# Main.net
KiCad netlist of a schematic drawn in Altium Designer
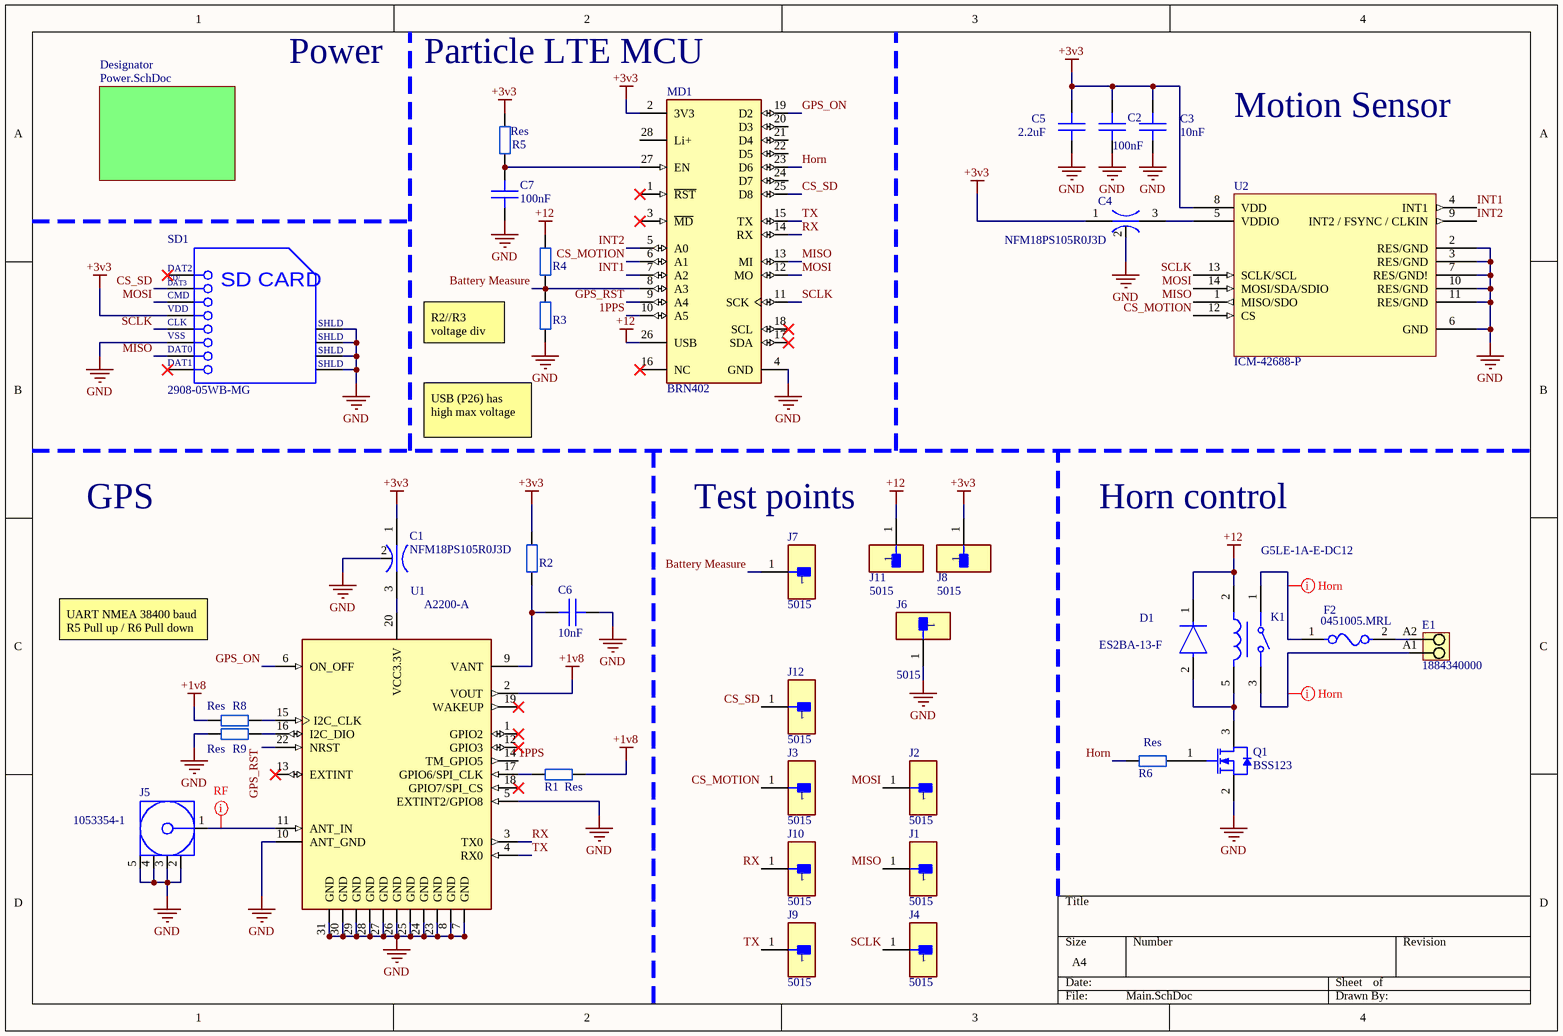
[diagram p0: Main.SchDoc]

(export (version "E")
  (design (tool "Eeschema 10.0.6"))
  (components
    (comp (ref "C1")
      (value "NFM18PS105R0J3D")
      (footprint "FP-NFM18-0_1-e0_05_0_35-MFG")
      (fields (field (name "VOLTAGE") "6.3V") (field (name "TOLERANCE") "20%"))
      (libsource (lib "Altium Content Vault") (part "2c8219d808f9f7a44d846a7a664b4f6"))
    )
    (comp (ref "C2")
      (value "100nF")
      (footprint "C0603 (1608)")
      (fields (field (name "Comment") "Cap SMD"))
      (libsource (lib "Moto Symbol Lib") (part "Cap SMD"))
    )
    (comp (ref "C3")
      (value "10nF")
      (footprint "C0603 (1608)")
      (fields (field (name "Comment") "Cap SMD"))
      (libsource (lib "Moto Symbol Lib") (part "Cap SMD"))
    )
    (comp (ref "C4")
      (value "NFM18PS105R0J3D")
      (footprint "FP-NFM18-0_1-e0_05_0_35-MFG")
      (fields (field (name "VOLTAGE") "6.3V") (field (name "TOLERANCE") "20%"))
      (libsource (lib "Altium Content Vault") (part "2c8219d808f9f7a44d846a7a664b4f6"))
    )
    (comp (ref "C5")
      (value "2.2uF")
      (footprint "C0603 (1608)")
      (fields (field (name "Comment") "Cap SMD"))
      (libsource (lib "Moto Symbol Lib") (part "Cap SMD"))
    )
    (comp (ref "C6")
      (value "10nF")
      (footprint "C0603 (1608)")
      (fields (field (name "Comment") "Cap SMD"))
      (libsource (lib "Moto Symbol Lib") (part "Cap SMD"))
    )
    (comp (ref "C7")
      (value "100nF")
      (footprint "C0603 (1608)")
      (fields (field (name "Comment") "Cap SMD"))
      (libsource (lib "Moto Symbol Lib") (part "Cap SMD"))
    )
    (comp (ref "D1")
      (value "ES2BA-13-F")
      (footprint "FP-SMA-MFG")
      (description "DIODE GEN PURP 100V 2A SMA")
      (fields
        (field (name "MANUFACTURER") "Diodes Inc.")
        (field (name "OCTOPART") "https://octopart.com/es2ba-13-f-diodes+inc.-14402013")
      )
      (libsource (lib "Altium Content Vault") (part "d7152d700b627762746794eb795d46e"))
    )
    (comp (ref "E1")
      (value "1884340000")
      (footprint "LSF_SMT_5_00_135_02")
      (description "OMNIMATE Signal - series LSF")
      (fields (field (name "MANUFACTURER") "Weidmueller"))
      (libsource (lib "Altium Content Vault") (part "Terminal_02_1x02"))
    )
    (comp (ref "F2")
      (value "0451005.MRL")
      (footprint "FP-0451-MFG")
      (description "FUSE BRD MNT 5A 125VAC/VDC 2SMD")
      (fields
        (field (name "OCTOPART") "https://octopart.com/0451005.mrl-littelfuse-566389")
        (field (name "MANUFACTURER") "Littelfuse Inc")
      )
      (libsource (lib "Altium Content Vault") (part "5bcf9b9f640e542cf0359d10258e979"))
    )
    (comp (ref "J1")
      (value "5015")
      (footprint "FP-5015-MFG")
      (description "PC TEST POINT MINIATURE")
      (fields
        (field (name "MANUFACTURER") "keystone")
        (field (name "OCTOPART") "https://octopart.com/5015-keystone-3822")
      )
      (libsource (lib "Altium Content Vault") (part "dd45045ce8184df9e99e12baf3f412c"))
    )
    (comp (ref "J2")
      (value "5015")
      (footprint "FP-5015-MFG")
      (description "PC TEST POINT MINIATURE")
      (fields
        (field (name "MANUFACTURER") "keystone")
        (field (name "OCTOPART") "https://octopart.com/5015-keystone-3822")
      )
      (libsource (lib "Altium Content Vault") (part "dd45045ce8184df9e99e12baf3f412c"))
    )
    (comp (ref "J3")
      (value "5015")
      (footprint "FP-5015-MFG")
      (description "PC TEST POINT MINIATURE")
      (fields
        (field (name "MANUFACTURER") "keystone")
        (field (name "OCTOPART") "https://octopart.com/5015-keystone-3822")
      )
      (libsource (lib "Altium Content Vault") (part "dd45045ce8184df9e99e12baf3f412c"))
    )
    (comp (ref "J4")
      (value "5015")
      (footprint "FP-5015-MFG")
      (description "PC TEST POINT MINIATURE")
      (fields
        (field (name "MANUFACTURER") "keystone")
        (field (name "OCTOPART") "https://octopart.com/5015-keystone-3822")
      )
      (libsource (lib "Altium Content Vault") (part "dd45045ce8184df9e99e12baf3f412c"))
    )
    (comp (ref "J5")
      (value "1053354-1")
      (footprint "TECO-1053354-1_V")
      (description "Female Coaxial Connector, Pitch 2.55 mm, Height 9.5 mm, Tail Length 3.9 mm, RoHS, Bulk")
      (fields (field (name "MANUFACTURER") "TE Connectivity"))
      (libsource (lib "Altium Content Vault") (part "CN-S-4F-RF5"))
    )
    (comp (ref "J6")
      (value "5015")
      (footprint "FP-5015-MFG")
      (description "PC TEST POINT MINIATURE")
      (fields
        (field (name "MANUFACTURER") "keystone")
        (field (name "OCTOPART") "https://octopart.com/5015-keystone-3822")
      )
      (libsource (lib "") (part "dd45045ce8184df9e99e12baf3f412c_1"))
    )
    (comp (ref "J7")
      (value "5015")
      (footprint "FP-5015-MFG")
      (description "PC TEST POINT MINIATURE")
      (fields
        (field (name "MANUFACTURER") "keystone")
        (field (name "OCTOPART") "https://octopart.com/5015-keystone-3822")
      )
      (libsource (lib "Altium Content Vault") (part "dd45045ce8184df9e99e12baf3f412c"))
    )
    (comp (ref "J8")
      (value "5015")
      (footprint "FP-5015-MFG")
      (description "PC TEST POINT MINIATURE")
      (fields
        (field (name "MANUFACTURER") "keystone")
        (field (name "OCTOPART") "https://octopart.com/5015-keystone-3822")
      )
      (libsource (lib "") (part "dd45045ce8184df9e99e12baf3f412c_2"))
    )
    (comp (ref "J9")
      (value "5015")
      (footprint "FP-5015-MFG")
      (description "PC TEST POINT MINIATURE")
      (fields
        (field (name "MANUFACTURER") "keystone")
        (field (name "OCTOPART") "https://octopart.com/5015-keystone-3822")
      )
      (libsource (lib "Altium Content Vault") (part "dd45045ce8184df9e99e12baf3f412c"))
    )
    (comp (ref "J10")
      (value "5015")
      (footprint "FP-5015-MFG")
      (description "PC TEST POINT MINIATURE")
      (fields
        (field (name "MANUFACTURER") "keystone")
        (field (name "OCTOPART") "https://octopart.com/5015-keystone-3822")
      )
      (libsource (lib "Altium Content Vault") (part "dd45045ce8184df9e99e12baf3f412c"))
    )
    (comp (ref "J11")
      (value "5015")
      (footprint "FP-5015-MFG")
      (description "PC TEST POINT MINIATURE")
      (fields
        (field (name "MANUFACTURER") "keystone")
        (field (name "OCTOPART") "https://octopart.com/5015-keystone-3822")
      )
      (libsource (lib "") (part "dd45045ce8184df9e99e12baf3f412c_2"))
    )
    (comp (ref "J12")
      (value "5015")
      (footprint "FP-5015-MFG")
      (description "PC TEST POINT MINIATURE")
      (fields
        (field (name "MANUFACTURER") "keystone")
        (field (name "OCTOPART") "https://octopart.com/5015-keystone-3822")
      )
      (libsource (lib "Altium Content Vault") (part "dd45045ce8184df9e99e12baf3f412c"))
    )
    (comp (ref "K1")
      (value "G5LE-1A-E-DC12")
      (footprint "FP-G5LE-1A-E-DC12-MFG")
      (description "RELAY GEN PURPOSE SPST 16A 12V")
      (libsource (lib "Altium Content Vault") (part "6e495d724dc645a58f977e2129b87ff"))
    )
    (comp (ref "MD1")
      (value "BRN402")
      (footprint "FP-BRN402-0")
      (description "BORON LTE")
      (fields
        (field (name "MANUFACTURER") "Particle")
        (field (name "OCTOPART") "https://octopart.com/brn402-particle-96116406")
      )
      (libsource (lib "Altium Content Vault") (part "69875060e2d83e17e1308076102c484"))
    )
    (comp (ref "Q1")
      (value "BSS123")
      (footprint "FAIR-SOT23-3_V")
      (fields (field (name "MANUFACTURER") "Fairchild"))
      (libsource (lib "Altium Content Vault") (part "NEMOS-GSD-3"))
    )
    (comp (ref "R1")
      (value "Res")
      (footprint "R0603 (1608)")
      (libsource (lib "Moto Symbol Lib") (part "Resistor EU"))
    )
    (comp (ref "R2")
      (value "Res")
      (footprint "R0603 (1608)")
      (libsource (lib "Moto Symbol Lib") (part "Resistor EU"))
    )
    (comp (ref "R3")
      (value "Res")
      (footprint "R0603 (1608)")
      (libsource (lib "Moto Symbol Lib") (part "Resistor EU"))
    )
    (comp (ref "R4")
      (value "Res")
      (footprint "R0603 (1608)")
      (libsource (lib "Moto Symbol Lib") (part "Resistor EU"))
    )
    (comp (ref "R5")
      (value "Res")
      (footprint "R0603 (1608)")
      (libsource (lib "Moto Symbol Lib") (part "Resistor EU"))
    )
    (comp (ref "R6")
      (value "Res")
      (footprint "R0603 (1608)")
      (libsource (lib "Moto Symbol Lib") (part "Resistor EU"))
    )
    (comp (ref "R8")
      (value "Res")
      (footprint "R0603 (1608)")
      (libsource (lib "Moto Symbol Lib") (part "Resistor EU"))
    )
    (comp (ref "R9")
      (value "Res")
      (footprint "R0603 (1608)")
      (libsource (lib "Moto Symbol Lib") (part "Resistor EU"))
    )
    (comp (ref "SD1")
      (value "2908-05WB-MG")
      (footprint "3M-2908-05WB-MG_V")
      (description "Card Connector Micro-SD, 500 VAC, 100 mOhm Min, 0.5 A, RoHS, Tape and Reel")
      (fields (field (name "MANUFACTURER") "3M"))
      (libsource (lib "Altium Content Vault") (part "CN-SD-8-4S"))
    )
    (comp (ref "U1")
      (value "A2200-A")
      (footprint "XCVR_A2200-A")
      (description "SiRFstarIVâ„¢ RF Receiver GPS 1.575GHz -163dBm 115.2kbps Module")
      (fields (field (name "MF") "Maestro Wireless"))
      (libsource (lib "Moto Symbol Lib") (part "A2200-A"))
    )
    (comp (ref "U2")
      (value "ICM-42688-P")
      (footprint "ICM-42688-P")
      (libsource (lib "Moto Symbol Lib") (part "ICM-42688-P"))
    )
  )
  (nets
    (net (code "1") (name "+1v8") (class "Default")
      (node (ref "R1") (pin "1") (pinfunction "1_1") (pintype "power_in"))
      (node (ref "R8") (pin "2") (pinfunction "2_2") (pintype "power_in"))
      (node (ref "U1") (pin "2") (pinfunction "VOUT_2") (pintype "output"))
    )
    (net (code "2") (name "+3v3") (class "Default")
      (node (ref "C1") (pin "1") (pinfunction "Input_1") (pintype "passive"))
      (node (ref "C2") (pin "2") (pinfunction "2_2") (pintype "power_in"))
      (node (ref "C3") (pin "2") (pinfunction "2_2") (pintype "power_in"))
      (node (ref "C4") (pin "1") (pinfunction "Input_1") (pintype "passive"))
      (node (ref "C5") (pin "2") (pinfunction "2_2") (pintype "power_in"))
      (node (ref "J8") (pin "1") (pinfunction "1_1") (pintype "passive"))
      (node (ref "MD1") (pin "2") (pinfunction "3V3_2") (pintype "power_in"))
      (node (ref "R2") (pin "2") (pinfunction "2_2") (pintype "power_in"))
      (node (ref "R5") (pin "2") (pinfunction "2_2") (pintype "power_in"))
      (node (ref "SD1") (pin "4") (pinfunction "VDD_4") (pintype "passive"))
      (node (ref "U2") (pin "8") (pinfunction "VDD_8") (pintype "power_in"))
    )
    (net (code "3") (name "+12") (class "Default")
      (node (ref "D1") (pin "1") (pinfunction "C_1") (pintype "passive"))
      (node (ref "J11") (pin "1") (pinfunction "1_1") (pintype "passive"))
      (node (ref "K1") (pin "2") (pinfunction "2_2") (pintype "passive"))
      (node (ref "MD1") (pin "26") (pinfunction "USB_26") (pintype "passive"))
      (node (ref "R4") (pin "2") (pinfunction "2_2") (pintype "power_in"))
    )
    (net (code "4") (name "/1PPS") (class "Default")
      (node (ref "MD1") (pin "10") (pinfunction "A5_10") (pintype "bidirectional"))
      (node (ref "U1") (pin "14") (pinfunction "TM_GPIO5_14") (pintype "output"))
    )
    (net (code "5") (name "/Battery Measure") (class "Default")
      (node (ref "J7") (pin "1") (pinfunction "1_1") (pintype "passive"))
      (node (ref "MD1") (pin "8") (pinfunction "A3_8") (pintype "bidirectional"))
      (node (ref "R3") (pin "2") (pinfunction "2_2") (pintype "power_in"))
      (node (ref "R4") (pin "1") (pinfunction "1_1") (pintype "power_in"))
    )
    (net (code "6") (name "/CS_MOTION") (class "Default")
      (node (ref "J3") (pin "1") (pinfunction "1_1") (pintype "passive"))
      (node (ref "MD1") (pin "6") (pinfunction "A1_6") (pintype "bidirectional"))
      (node (ref "U2") (pin "12") (pinfunction "CS_12") (pintype "input"))
    )
    (net (code "7") (name "/CS_SD") (class "Default")
      (node (ref "J12") (pin "1") (pinfunction "1_1") (pintype "passive"))
      (node (ref "MD1") (pin "25") (pinfunction "D8_25") (pintype "bidirectional"))
      (node (ref "SD1") (pin "2") (pinfunction "CD/DAT3_2") (pintype "passive"))
    )
    (net (code "8") (name "/GPS_ON") (class "Default")
      (node (ref "MD1") (pin "19") (pinfunction "D2_19") (pintype "bidirectional"))
      (node (ref "U1") (pin "6") (pinfunction "ON_OFF_6") (pintype "input"))
    )
    (net (code "9") (name "/GPS_RST") (class "Default")
      (node (ref "MD1") (pin "9") (pinfunction "A4_9") (pintype "bidirectional"))
      (node (ref "U1") (pin "22") (pinfunction "NRST_22") (pintype "input"))
    )
    (net (code "10") (name "/Horn") (class "Default")
      (node (ref "MD1") (pin "23") (pinfunction "D6_23") (pintype "bidirectional"))
      (node (ref "R6") (pin "2") (pinfunction "2_2") (pintype "power_in"))
    )
    (net (code "11") (name "/INT1") (class "Default")
      (node (ref "MD1") (pin "7") (pinfunction "A2_7") (pintype "bidirectional"))
      (node (ref "U2") (pin "4") (pinfunction "INT1_4") (pintype "output"))
    )
    (net (code "12") (name "/INT2") (class "Default")
      (node (ref "MD1") (pin "5") (pinfunction "A0_5") (pintype "bidirectional"))
      (node (ref "U2") (pin "9") (pinfunction "INT2_/_FSYNC_/_CLKIN_9") (pintype "output"))
    )
    (net (code "13") (name "/MISO") (class "Default")
      (node (ref "J1") (pin "1") (pinfunction "1_1") (pintype "passive"))
      (node (ref "MD1") (pin "13") (pinfunction "MI_13") (pintype "bidirectional"))
      (node (ref "SD1") (pin "7") (pinfunction "DAT0_7") (pintype "passive"))
      (node (ref "U2") (pin "1") (pinfunction "MISO/SDO_1") (pintype "output"))
    )
    (net (code "14") (name "/MOSI") (class "Default")
      (node (ref "J2") (pin "1") (pinfunction "1_1") (pintype "passive"))
      (node (ref "MD1") (pin "12") (pinfunction "MO_12") (pintype "bidirectional"))
      (node (ref "SD1") (pin "3") (pinfunction "CMD_3") (pintype "passive"))
      (node (ref "U2") (pin "14") (pinfunction "MOSI/SDA/SDIO_14") (pintype "input"))
    )
    (net (code "15") (name "/RX") (class "Default")
      (node (ref "J10") (pin "1") (pinfunction "1_1") (pintype "passive"))
      (node (ref "MD1") (pin "14") (pinfunction "RX_14") (pintype "bidirectional"))
      (node (ref "U1") (pin "3") (pinfunction "TX0_3") (pintype "output"))
    )
    (net (code "16") (name "/SCLK") (class "Default")
      (node (ref "J4") (pin "1") (pinfunction "1_1") (pintype "passive"))
      (node (ref "MD1") (pin "11") (pinfunction "SCK_11") (pintype "bidirectional"))
      (node (ref "SD1") (pin "5") (pinfunction "CLK_5") (pintype "passive"))
      (node (ref "U2") (pin "13") (pinfunction "SCLK/SCL_13") (pintype "input"))
    )
    (net (code "17") (name "/TX") (class "Default")
      (node (ref "J9") (pin "1") (pinfunction "1_1") (pintype "passive"))
      (node (ref "MD1") (pin "15") (pinfunction "TX_15") (pintype "bidirectional"))
      (node (ref "U1") (pin "4") (pinfunction "RX0_4") (pintype "input"))
    )
    (net (code "18") (name "GND") (class "Default")
      (node (ref "C1") (pin "2") (pinfunction "GND_2") (pintype "passive"))
      (node (ref "C2") (pin "1") (pinfunction "1_1") (pintype "power_in"))
      (node (ref "C3") (pin "1") (pinfunction "1_1") (pintype "power_in"))
      (node (ref "C4") (pin "2") (pinfunction "GND_2") (pintype "passive"))
      (node (ref "C5") (pin "1") (pinfunction "1_1") (pintype "power_in"))
      (node (ref "C6") (pin "1") (pinfunction "1_1") (pintype "power_in"))
      (node (ref "C7") (pin "1") (pinfunction "1_1") (pintype "power_in"))
      (node (ref "J5") (pin "2") (pinfunction "2_2") (pintype "passive"))
      (node (ref "J5") (pin "3") (pinfunction "3_3") (pintype "passive"))
      (node (ref "J5") (pin "4") (pinfunction "4_4") (pintype "passive"))
      (node (ref "J5") (pin "5") (pinfunction "5_5") (pintype "passive"))
      (node (ref "J6") (pin "1") (pinfunction "1_1") (pintype "passive"))
      (node (ref "MD1") (pin "4") (pinfunction "GND_4") (pintype "power_in"))
      (node (ref "Q1") (pin "2") (pinfunction "S_2") (pintype "passive"))
      (node (ref "R3") (pin "1") (pinfunction "1_1") (pintype "power_in"))
      (node (ref "R9") (pin "2") (pinfunction "2_2") (pintype "power_in"))
      (node (ref "SD1") (pin "10") (pinfunction "SHLD_10") (pintype "passive"))
      (node (ref "SD1") (pin "11") (pinfunction "SHLD_11") (pintype "passive"))
      (node (ref "SD1") (pin "12") (pinfunction "SHLD_12") (pintype "passive"))
      (node (ref "SD1") (pin "6") (pinfunction "VSS_6") (pintype "passive"))
      (node (ref "SD1") (pin "9") (pinfunction "SHLD_9") (pintype "passive"))
      (node (ref "U1") (pin "10") (pinfunction "ANT_GND_10") (pintype "power_in"))
      (node (ref "U1") (pin "23") (pinfunction "GND_23") (pintype "power_in"))
      (node (ref "U1") (pin "24") (pinfunction "GND_24") (pintype "power_in"))
      (node (ref "U1") (pin "25") (pinfunction "GND_25") (pintype "power_in"))
      (node (ref "U1") (pin "26") (pinfunction "GND_26") (pintype "power_in"))
      (node (ref "U1") (pin "27") (pinfunction "GND_27") (pintype "power_in"))
      (node (ref "U1") (pin "28") (pinfunction "GND_28") (pintype "power_in"))
      (node (ref "U1") (pin "29") (pinfunction "GND_29") (pintype "power_in"))
      (node (ref "U1") (pin "30") (pinfunction "GND_30") (pintype "power_in"))
      (node (ref "U1") (pin "31") (pinfunction "GND_31") (pintype "power_in"))
      (node (ref "U1") (pin "5") (pinfunction "EXTINT2/GPIO8_5") (pintype "input"))
      (node (ref "U1") (pin "7") (pinfunction "GND_7") (pintype "power_in"))
      (node (ref "U1") (pin "8") (pinfunction "GND_8") (pintype "power_in"))
      (node (ref "U2") (pin "10") (pinfunction "RES/GND_10") (pintype "passive"))
      (node (ref "U2") (pin "11") (pinfunction "RES/GND_11") (pintype "passive"))
      (node (ref "U2") (pin "2") (pinfunction "RES/GND_2") (pintype "passive"))
      (node (ref "U2") (pin "3") (pinfunction "RES/GND_3") (pintype "passive"))
      (node (ref "U2") (pin "6") (pinfunction "GND_6") (pintype "power_in"))
      (node (ref "U2") (pin "7") (pinfunction "RES/GND!_7") (pintype "passive"))
    )
    (net (code "19") (name "Net-(C1-Output)") (class "Default")
      (node (ref "C1") (pin "3") (pinfunction "Output_3") (pintype "passive"))
      (node (ref "U1") (pin "20") (pinfunction "VCC3.3V_20") (pintype "power_in"))
    )
    (net (code "20") (name "Net-(C4-Output)") (class "Default")
      (node (ref "C4") (pin "3") (pinfunction "Output_3") (pintype "passive"))
      (node (ref "U2") (pin "5") (pinfunction "VDDIO_5") (pintype "power_in"))
    )
    (net (code "21") (name "Net-(D1-A)") (class "Default")
      (node (ref "D1") (pin "2") (pinfunction "A_2") (pintype "passive"))
      (node (ref "K1") (pin "5") (pinfunction "5_5") (pintype "passive"))
      (node (ref "Q1") (pin "3") (pinfunction "D_3") (pintype "passive"))
    )
    (net (code "22") (name "Net-(E1-PadA1)") (class "Default")
      (node (ref "E1") (pin "A1") (pinfunction "A1_A1") (pintype "passive"))
      (node (ref "K1") (pin "3") (pinfunction "3_3") (pintype "passive"))
    )
    (net (code "23") (name "Net-(E1-PadA2)") (class "Default")
      (node (ref "E1") (pin "A2") (pinfunction "A2_A2") (pintype "passive"))
      (node (ref "F2") (pin "2") (pinfunction "2_2") (pintype "passive"))
    )
    (net (code "24") (name "Net-(F2-Pad1)") (class "Default")
      (node (ref "F2") (pin "1") (pinfunction "1_1") (pintype "passive"))
      (node (ref "K1") (pin "1") (pinfunction "1_1") (pintype "passive"))
    )
    (net (code "25") (name "Net-(MD1-EN)") (class "Default")
      (node (ref "C7") (pin "2") (pinfunction "2_2") (pintype "power_in"))
      (node (ref "MD1") (pin "27") (pinfunction "EN_27") (pintype "input"))
      (node (ref "R5") (pin "1") (pinfunction "1_1") (pintype "power_in"))
    )
    (net (code "26") (name "Net-(Q1-G)") (class "Default")
      (node (ref "Q1") (pin "1") (pinfunction "G_1") (pintype "passive"))
      (node (ref "R6") (pin "1") (pinfunction "1_1") (pintype "power_in"))
    )
    (net (code "27") (name "Net-(U1-ANT_IN)") (class "Default")
      (node (ref "J5") (pin "1") (pinfunction "1_1") (pintype "passive"))
      (node (ref "U1") (pin "11") (pinfunction "ANT_IN_11") (pintype "input"))
    )
    (net (code "28") (name "Net-(U1-GPIO6{slash}SPI_CLK)") (class "Default")
      (node (ref "R1") (pin "2") (pinfunction "2_2") (pintype "power_in"))
      (node (ref "U1") (pin "17") (pinfunction "GPIO6/SPI_CLK_17") (pintype "input"))
    )
    (net (code "29") (name "Net-(U1-I2C_CLK)") (class "Default")
      (node (ref "R8") (pin "1") (pinfunction "1_1") (pintype "power_in"))
      (node (ref "U1") (pin "15") (pinfunction "I2C_CLK_15") (pintype "input"))
    )
    (net (code "30") (name "Net-(U1-I2C_DIO)") (class "Default")
      (node (ref "R9") (pin "1") (pinfunction "1_1") (pintype "power_in"))
      (node (ref "U1") (pin "16") (pinfunction "I2C_DIO_16") (pintype "bidirectional"))
    )
    (net (code "31") (name "Net-(U1-VANT)") (class "Default")
      (node (ref "C6") (pin "2") (pinfunction "2_2") (pintype "power_in"))
      (node (ref "R2") (pin "1") (pinfunction "1_1") (pintype "power_in"))
      (node (ref "U1") (pin "9") (pinfunction "VANT_9") (pintype "power_in"))
    )
    (net (code "32") (name "unconnected-(MD1-D3-Pad20)") (class "Default")
      (node (ref "MD1") (pin "20") (pinfunction "D3_20") (pintype "bidirectional"))
    )
    (net (code "33") (name "unconnected-(MD1-D4-Pad21)") (class "Default")
      (node (ref "MD1") (pin "21") (pinfunction "D4_21") (pintype "bidirectional"))
    )
    (net (code "34") (name "unconnected-(MD1-D5-Pad22)") (class "Default")
      (node (ref "MD1") (pin "22") (pinfunction "D5_22") (pintype "bidirectional"))
    )
    (net (code "35") (name "unconnected-(MD1-D7-Pad24)") (class "Default")
      (node (ref "MD1") (pin "24") (pinfunction "D7_24") (pintype "bidirectional"))
    )
    (net (code "36") (name "unconnected-(MD1-Li+-Pad28)") (class "Default")
      (node (ref "MD1") (pin "28") (pinfunction "Li+_28") (pintype "power_in"))
    )
    (net (code "37") (name "unconnected-(MD1-NC-Pad16)") (class "Default")
      (node (ref "MD1") (pin "16") (pinfunction "NC_16") (pintype "passive+no_connect"))
    )
    (net (code "38") (name "unconnected-(MD1-SCL-Pad18)") (class "Default")
      (node (ref "MD1") (pin "18") (pinfunction "SCL_18") (pintype "bidirectional+no_connect"))
    )
    (net (code "39") (name "unconnected-(MD1-SDA-Pad17)") (class "Default")
      (node (ref "MD1") (pin "17") (pinfunction "SDA_17") (pintype "bidirectional+no_connect"))
    )
    (net (code "40") (name "unconnected-(MD1-~{MD}-Pad3)") (class "Default")
      (node (ref "MD1") (pin "3") (pinfunction "~{MD}_3") (pintype "input+no_connect"))
    )
    (net (code "41") (name "unconnected-(MD1-~{RST}-Pad1)") (class "Default")
      (node (ref "MD1") (pin "1") (pinfunction "~{RST}_1") (pintype "input+no_connect"))
    )
    (net (code "42") (name "unconnected-(SD1-DAT1-Pad8)") (class "Default")
      (node (ref "SD1") (pin "8") (pinfunction "DAT1_8") (pintype "passive+no_connect"))
    )
    (net (code "43") (name "unconnected-(SD1-DAT2-Pad1)") (class "Default")
      (node (ref "SD1") (pin "1") (pinfunction "DAT2_1") (pintype "passive+no_connect"))
    )
    (net (code "44") (name "unconnected-(U1-EXTINT-Pad13)") (class "Default")
      (node (ref "U1") (pin "13") (pinfunction "EXTINT_13") (pintype "bidirectional+no_connect"))
    )
    (net (code "45") (name "unconnected-(U1-GPIO2-Pad1)") (class "Default")
      (node (ref "U1") (pin "1") (pinfunction "GPIO2_1") (pintype "bidirectional+no_connect"))
    )
    (net (code "46") (name "unconnected-(U1-GPIO3-Pad12)") (class "Default")
      (node (ref "U1") (pin "12") (pinfunction "GPIO3_12") (pintype "bidirectional+no_connect"))
    )
    (net (code "47") (name "unconnected-(U1-GPIO7{slash}SPI_CS-Pad18)") (class "Default")
      (node (ref "U1") (pin "18") (pinfunction "GPIO7/SPI_CS_18") (pintype "input+no_connect"))
    )
    (net (code "48") (name "unconnected-(U1-WAKEUP-Pad19)") (class "Default")
      (node (ref "U1") (pin "19") (pinfunction "WAKEUP_19") (pintype "output+no_connect"))
    )
  )
)
